# Adafruit_Flora_Si1145.net
KiCad netlist of a schematic drawn in EAGLE
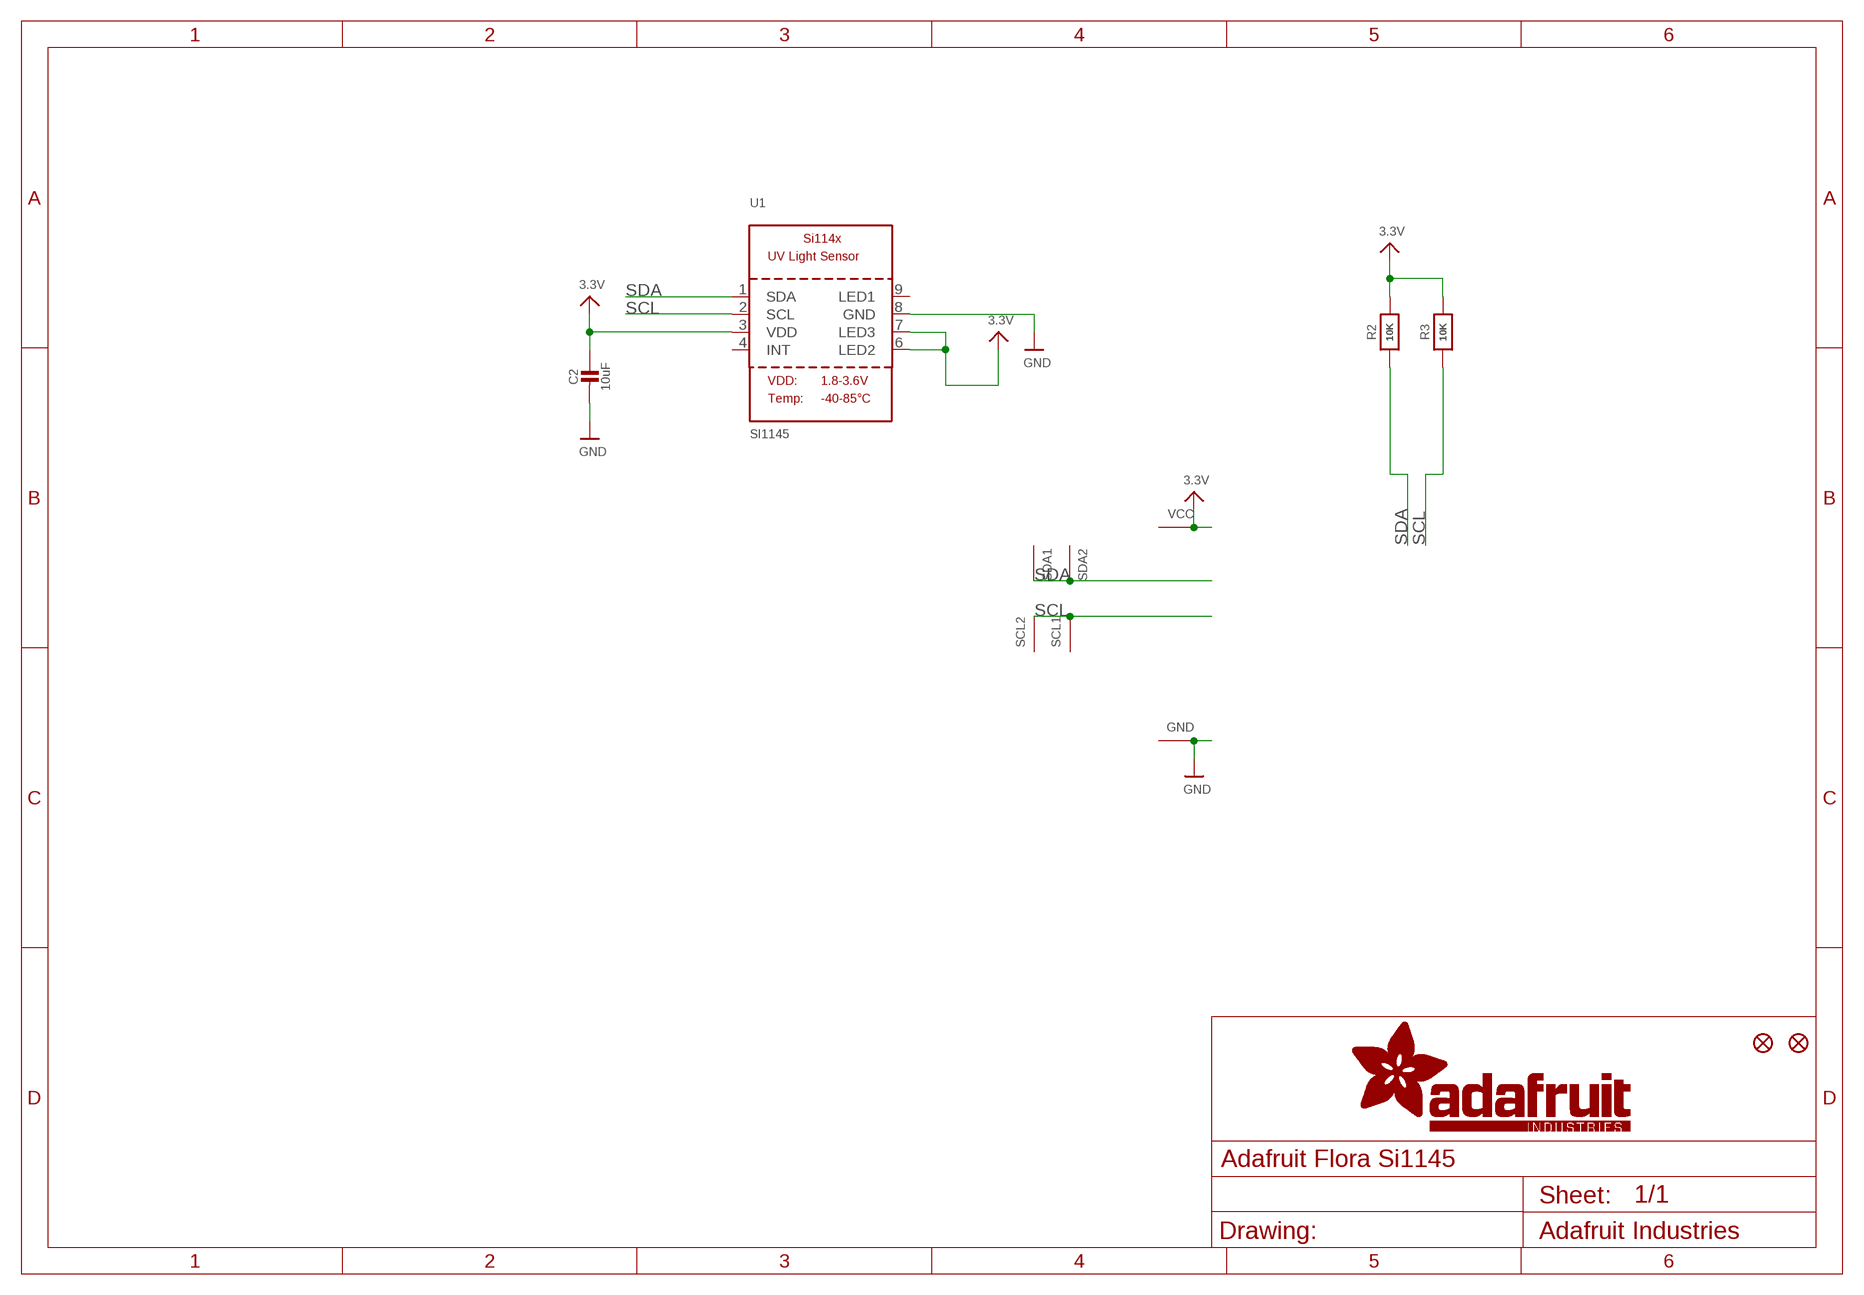
[diagram p0: schematic, sheet 1]

(export (version "E")
  (design (tool "Eeschema 10.0.6"))
  (components
    (comp (ref "C2")
      (value "10uF")
      (footprint "eagle-import:0805-NO")
      (libsource (lib "eagle-import") (part "CAP_CERAMIC0805-NOOUTLINE"))
    )
    (comp (ref "FID1")
      (value "FIDUCIAL\"\"")
      (footprint "eagle-import:FIDUCIAL_1MM")
      (libsource (lib "eagle-import") (part "FIDUCIAL{dblquote}{dblquote}"))
    )
    (comp (ref "FID2")
      (value "FIDUCIAL\"\"")
      (footprint "eagle-import:FIDUCIAL_1MM")
      (libsource (lib "eagle-import") (part "FIDUCIAL{dblquote}{dblquote}"))
    )
    (comp (ref "GND")
      (value "SEWTAP0.5IN")
      (footprint "eagle-import:SEWINGTAP_0.5")
      (libsource (lib "eagle-import") (part "SEWTAP0.5IN"))
    )
    (comp (ref "R2")
      (value "10K")
      (footprint "eagle-import:0805-NO")
      (libsource (lib "eagle-import") (part "RESISTOR0805_NOOUTLINE"))
    )
    (comp (ref "R3")
      (value "10K")
      (footprint "eagle-import:0805-NO")
      (libsource (lib "eagle-import") (part "RESISTOR0805_NOOUTLINE"))
    )
    (comp (ref "SCL1")
      (value "SEWTAP0.5IN")
      (footprint "eagle-import:SEWINGTAP_0.5")
      (libsource (lib "eagle-import") (part "SEWTAP0.5IN"))
    )
    (comp (ref "SCL2")
      (value "SEWTAP0.5IN")
      (footprint "eagle-import:SEWINGTAP_0.5")
      (libsource (lib "eagle-import") (part "SEWTAP0.5IN"))
    )
    (comp (ref "SDA1")
      (value "SEWTAP0.5IN")
      (footprint "eagle-import:SEWINGTAP_0.5")
      (libsource (lib "eagle-import") (part "SEWTAP0.5IN"))
    )
    (comp (ref "SDA2")
      (value "SEWTAP0.5IN")
      (footprint "eagle-import:SEWINGTAP_0.5")
      (libsource (lib "eagle-import") (part "SEWTAP0.5IN"))
    )
    (comp (ref "U1")
      (value "SI1145")
      (footprint "eagle-import:SI114X")
      (libsource (lib "eagle-import") (part "SI114X"))
    )
    (comp (ref "VCC")
      (value "SEWTAP0.5IN")
      (footprint "eagle-import:SEWINGTAP_0.5")
      (libsource (lib "eagle-import") (part "SEWTAP0.5IN"))
    )
  )
  (nets
    (net (code "1") (name "/SCL") (class "Default")
      (node (ref "R3") (pin "1") (pinfunction "1_1") (pintype "passive"))
      (node (ref "SCL1") (pin "TAP") (pinfunction "SEW_TAP") (pintype "bidirectional"))
      (node (ref "SCL2") (pin "TAP") (pinfunction "SEW_TAP") (pintype "bidirectional"))
      (node (ref "U1") (pin "2") (pinfunction "SCL_2") (pintype "input"))
    )
    (net (code "2") (name "/SDA") (class "Default")
      (node (ref "R2") (pin "1") (pinfunction "1_1") (pintype "passive"))
      (node (ref "SDA1") (pin "TAP") (pinfunction "SEW_TAP") (pintype "bidirectional"))
      (node (ref "SDA2") (pin "TAP") (pinfunction "SEW_TAP") (pintype "bidirectional"))
      (node (ref "U1") (pin "1") (pinfunction "SDA_1") (pintype "bidirectional"))
    )
    (net (code "3") (name "3.3V") (class "Default")
      (node (ref "C2") (pin "1") (pinfunction "1_1") (pintype "passive"))
      (node (ref "R2") (pin "2") (pinfunction "2_2") (pintype "passive"))
      (node (ref "R3") (pin "2") (pinfunction "2_2") (pintype "passive"))
      (node (ref "U1") (pin "3") (pinfunction "VDD_3") (pintype "power_in"))
      (node (ref "U1") (pin "6") (pinfunction "LED2_6") (pintype "open_collector"))
      (node (ref "U1") (pin "7") (pinfunction "LED3_7") (pintype "open_collector"))
      (node (ref "VCC") (pin "TAP") (pinfunction "SEW_TAP") (pintype "bidirectional"))
    )
    (net (code "4") (name "GND") (class "Default")
      (node (ref "C2") (pin "2") (pinfunction "2_2") (pintype "passive"))
      (node (ref "GND") (pin "TAP") (pinfunction "SEW_TAP") (pintype "bidirectional"))
      (node (ref "U1") (pin "8") (pinfunction "GND_8") (pintype "power_in"))
    )
    (net (code "5") (name "unconnected-(U1-INT-Pad4)") (class "Default")
      (node (ref "U1") (pin "4") (pinfunction "INT_4") (pintype "open_collector"))
    )
    (net (code "6") (name "unconnected-(U1-LED1-Pad9)") (class "Default")
      (node (ref "U1") (pin "9") (pinfunction "LED1_9") (pintype "open_collector"))
    )
  )
)
